# Schematic.net
KiCad netlist of a schematic drawn in EasyEDA
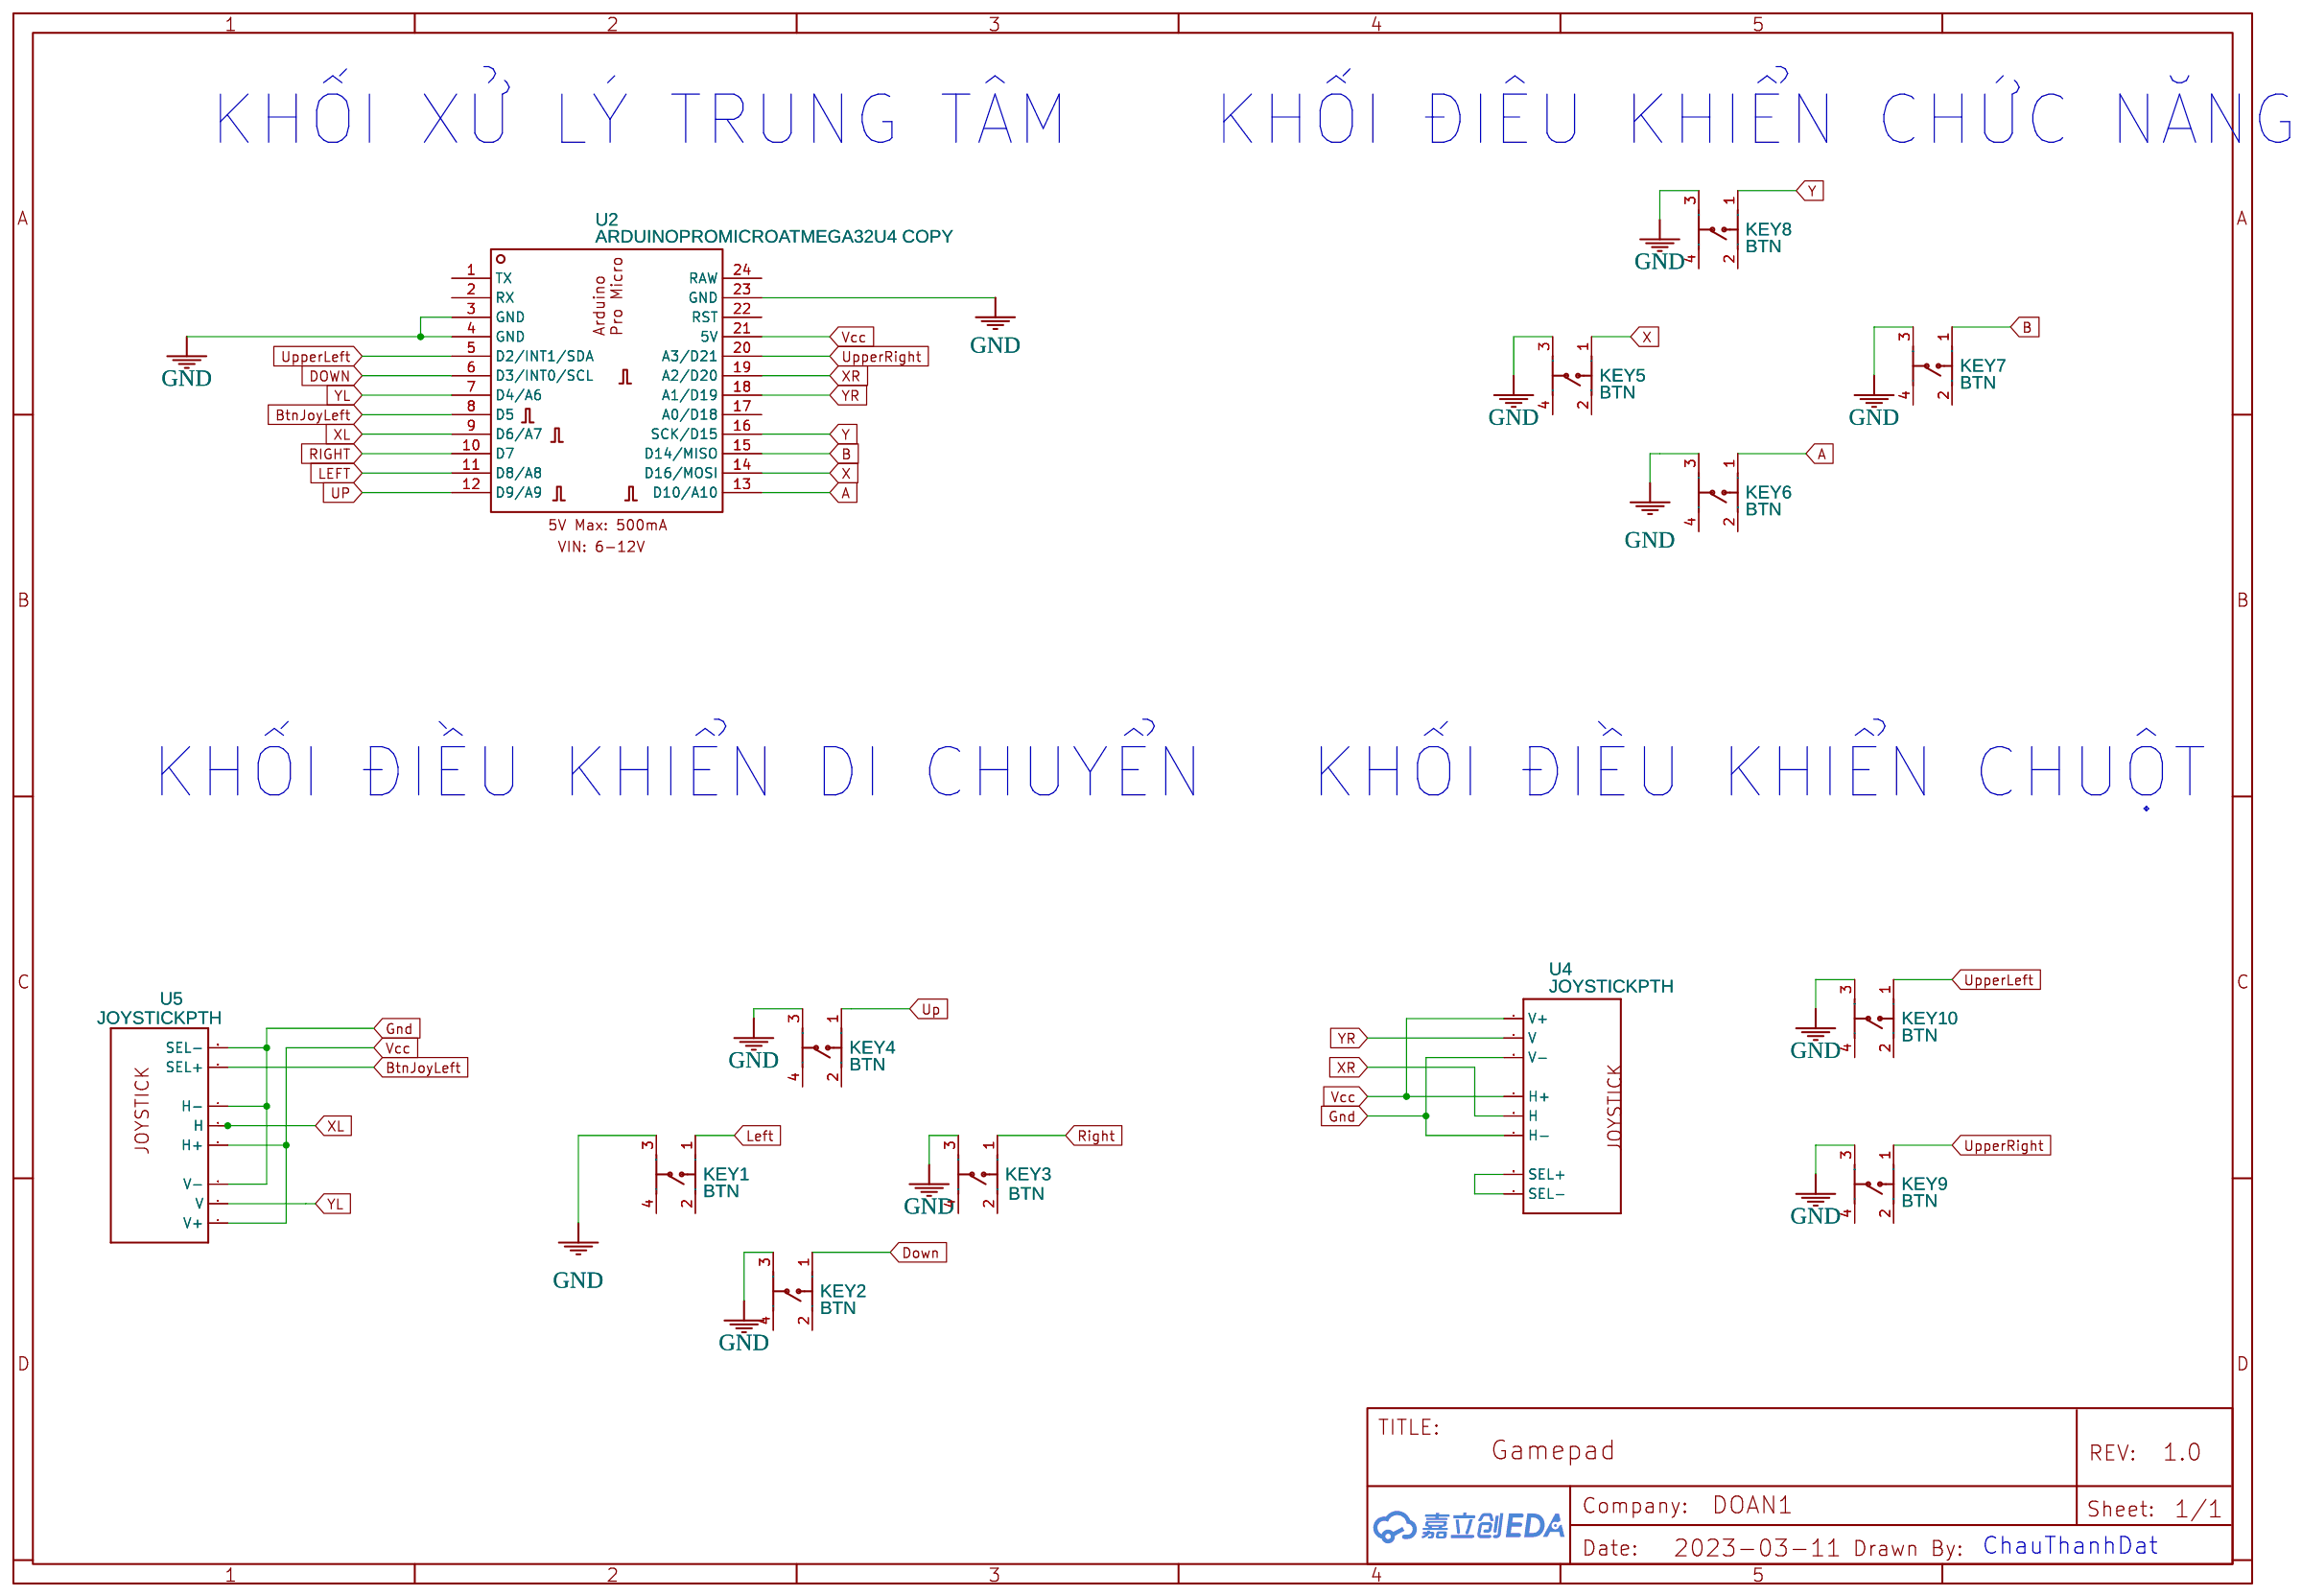
[diagram p0: schematic sheet]

(export (version "E")
  (design (tool "Eeschema 10.0.6"))
  (components
    (comp (ref "KEY1")
      (value "BTN")
      (fields
        (field (name "BOM_Manufacturer Part") "4pinTACTPCBTHTPushButton")
        (field (name "BOM_Supplier Part") "C9900003768")
      )
      (libsource (lib "") (part "4PINTACTPCBTHTPUSHBUTTON"))
    )
    (comp (ref "KEY2")
      (value "BTN")
      (fields
        (field (name "BOM_Manufacturer Part") "4pinTACTPCBTHTPushButton")
        (field (name "BOM_Supplier Part") "C9900003768")
      )
      (libsource (lib "") (part "4PINTACTPCBTHTPUSHBUTTON"))
    )
    (comp (ref "KEY3")
      (value "BTN")
      (fields
        (field (name "BOM_Manufacturer Part") "4pinTACTPCBTHTPushButton")
        (field (name "BOM_Supplier Part") "C9900003768")
      )
      (libsource (lib "") (part "4PINTACTPCBTHTPUSHBUTTON"))
    )
    (comp (ref "KEY4")
      (value "BTN")
      (fields
        (field (name "BOM_Manufacturer Part") "4pinTACTPCBTHTPushButton")
        (field (name "BOM_Supplier Part") "C9900003768")
      )
      (libsource (lib "") (part "4PINTACTPCBTHTPUSHBUTTON"))
    )
    (comp (ref "KEY5")
      (value "BTN")
      (fields
        (field (name "BOM_Manufacturer Part") "4pinTACTPCBTHTPushButton")
        (field (name "BOM_Supplier Part") "C9900003768")
      )
      (libsource (lib "") (part "4PINTACTPCBTHTPUSHBUTTON"))
    )
    (comp (ref "KEY6")
      (value "BTN")
      (fields
        (field (name "BOM_Manufacturer Part") "4pinTACTPCBTHTPushButton")
        (field (name "BOM_Supplier Part") "C9900003768")
      )
      (libsource (lib "") (part "4PINTACTPCBTHTPUSHBUTTON"))
    )
    (comp (ref "KEY7")
      (value "BTN")
      (fields
        (field (name "BOM_Manufacturer Part") "4pinTACTPCBTHTPushButton")
        (field (name "BOM_Supplier Part") "C9900003768")
      )
      (libsource (lib "") (part "4PINTACTPCBTHTPUSHBUTTON"))
    )
    (comp (ref "KEY8")
      (value "BTN")
      (fields
        (field (name "BOM_Manufacturer Part") "4pinTACTPCBTHTPushButton")
        (field (name "BOM_Supplier Part") "C9900003768")
      )
      (libsource (lib "") (part "4PINTACTPCBTHTPUSHBUTTON"))
    )
    (comp (ref "KEY9")
      (value "BTN")
      (fields
        (field (name "BOM_Manufacturer Part") "4pinTACTPCBTHTPushButton")
        (field (name "BOM_Supplier Part") "C9900003768")
      )
      (libsource (lib "") (part "4PINTACTPCBTHTPUSHBUTTON"))
    )
    (comp (ref "KEY10")
      (value "BTN")
      (fields
        (field (name "BOM_Manufacturer Part") "4pinTACTPCBTHTPushButton")
        (field (name "BOM_Supplier Part") "C9900003768")
      )
      (libsource (lib "") (part "4PINTACTPCBTHTPUSHBUTTON"))
    )
    (comp (ref "U2")
      (value "ARDUINOPROMICROATMEGA32U4 COPY")
      (libsource (lib "") (part "ARDUINOPROMICROATMEGA32U4 COPY"))
    )
    (comp (ref "U4") (value "JOYSTICKPTH") (libsource (lib "") (part "JOYSTICKPTH")))
    (comp (ref "U5") (value "JOYSTICKPTH") (libsource (lib "") (part "JOYSTICKPTH_1")))
  )
  (nets
    (net (code "1") (name "A") (class "Default")
      (node (ref "KEY6") (pin "1") (pinfunction "1_1") (pintype "unspecified"))
      (node (ref "U2") (pin "13") (pinfunction "D10/A10_13") (pintype "unspecified"))
    )
    (net (code "2") (name "B") (class "Default")
      (node (ref "KEY7") (pin "1") (pinfunction "1_1") (pintype "unspecified"))
      (node (ref "U2") (pin "15") (pinfunction "D14/MISO_15") (pintype "unspecified"))
    )
    (net (code "3") (name "BtnJoyLeft") (class "Default")
      (node (ref "U2") (pin "8") (pinfunction "D5_8") (pintype "unspecified"))
      (node (ref "U5") (pin "B1A") (pinfunction "SEL+_B1A") (pintype "unspecified"))
    )
    (net (code "4") (name "DOWN") (class "Default")
      (node (ref "U2") (pin "6") (pinfunction "D3/INT0/SCL_6") (pintype "unspecified"))
    )
    (net (code "5") (name "Down") (class "Default")
      (node (ref "KEY2") (pin "1") (pinfunction "1_1") (pintype "unspecified"))
    )
    (net (code "6") (name "GND") (class "Default")
      (node (ref "KEY1") (pin "3") (pinfunction "3_3") (pintype "unspecified"))
      (node (ref "KEY10") (pin "3") (pinfunction "3_3") (pintype "unspecified"))
      (node (ref "KEY2") (pin "3") (pinfunction "3_3") (pintype "unspecified"))
      (node (ref "KEY3") (pin "3") (pinfunction "3_3") (pintype "unspecified"))
      (node (ref "KEY4") (pin "3") (pinfunction "3_3") (pintype "unspecified"))
      (node (ref "KEY5") (pin "3") (pinfunction "3_3") (pintype "unspecified"))
      (node (ref "KEY6") (pin "3") (pinfunction "3_3") (pintype "unspecified"))
      (node (ref "KEY7") (pin "3") (pinfunction "3_3") (pintype "unspecified"))
      (node (ref "KEY8") (pin "3") (pinfunction "3_3") (pintype "unspecified"))
      (node (ref "KEY9") (pin "3") (pinfunction "3_3") (pintype "unspecified"))
      (node (ref "U2") (pin "23") (pinfunction "GND_23") (pintype "unspecified"))
      (node (ref "U2") (pin "3") (pinfunction "GND_3") (pintype "unspecified"))
      (node (ref "U2") (pin "4") (pinfunction "GND_4") (pintype "unspecified"))
    )
    (net (code "7") (name "Gnd") (class "Default")
      (node (ref "U4") (pin "H3") (pinfunction "H-_H3") (pintype "unspecified"))
      (node (ref "U4") (pin "V3") (pinfunction "V-_V3") (pintype "unspecified"))
      (node (ref "U5") (pin "B2A") (pinfunction "SEL-_B2A") (pintype "unspecified"))
      (node (ref "U5") (pin "H3") (pinfunction "H-_H3") (pintype "unspecified"))
      (node (ref "U5") (pin "V3") (pinfunction "V-_V3") (pintype "unspecified"))
    )
    (net (code "8") (name "LEFT") (class "Default")
      (node (ref "U2") (pin "11") (pinfunction "D8/A8_11") (pintype "unspecified"))
    )
    (net (code "9") (name "Left") (class "Default")
      (node (ref "KEY1") (pin "1") (pinfunction "1_1") (pintype "unspecified"))
    )
    (net (code "10") (name "Net-(U4-SEL+)") (class "Default")
      (node (ref "U4") (pin "B1A") (pinfunction "SEL+_B1A") (pintype "unspecified"))
      (node (ref "U4") (pin "B2A") (pinfunction "SEL-_B2A") (pintype "unspecified"))
    )
    (net (code "11") (name "RIGHT") (class "Default")
      (node (ref "U2") (pin "10") (pinfunction "D7_10") (pintype "unspecified"))
    )
    (net (code "12") (name "Right") (class "Default")
      (node (ref "KEY3") (pin "1") (pinfunction "1_1") (pintype "unspecified"))
    )
    (net (code "13") (name "UP") (class "Default")
      (node (ref "U2") (pin "12") (pinfunction "D9/A9_12") (pintype "unspecified"))
    )
    (net (code "14") (name "Up") (class "Default")
      (node (ref "KEY4") (pin "1") (pinfunction "1_1") (pintype "unspecified"))
    )
    (net (code "15") (name "UpperLeft") (class "Default")
      (node (ref "KEY10") (pin "1") (pinfunction "1_1") (pintype "unspecified"))
      (node (ref "U2") (pin "5") (pinfunction "D2/INT1/SDA_5") (pintype "unspecified"))
    )
    (net (code "16") (name "UpperRight") (class "Default")
      (node (ref "KEY9") (pin "1") (pinfunction "1_1") (pintype "unspecified"))
      (node (ref "U2") (pin "20") (pinfunction "A3/D21_20") (pintype "unspecified"))
    )
    (net (code "17") (name "Vcc") (class "Default")
      (node (ref "U2") (pin "21") (pinfunction "5V_21") (pintype "unspecified"))
      (node (ref "U4") (pin "H1") (pinfunction "H+_H1") (pintype "unspecified"))
      (node (ref "U4") (pin "V1") (pinfunction "V+_V1") (pintype "unspecified"))
      (node (ref "U5") (pin "H1") (pinfunction "H+_H1") (pintype "unspecified"))
      (node (ref "U5") (pin "V1") (pinfunction "V+_V1") (pintype "unspecified"))
    )
    (net (code "18") (name "X") (class "Default")
      (node (ref "KEY5") (pin "1") (pinfunction "1_1") (pintype "unspecified"))
      (node (ref "U2") (pin "14") (pinfunction "D16/MOSI_14") (pintype "unspecified"))
    )
    (net (code "19") (name "XL") (class "Default")
      (node (ref "U2") (pin "9") (pinfunction "D6/A7_9") (pintype "unspecified"))
      (node (ref "U5") (pin "H2") (pinfunction "H_H2") (pintype "unspecified"))
    )
    (net (code "20") (name "XR") (class "Default")
      (node (ref "U2") (pin "19") (pinfunction "A2/D20_19") (pintype "unspecified"))
      (node (ref "U4") (pin "H2") (pinfunction "H_H2") (pintype "unspecified"))
    )
    (net (code "21") (name "Y") (class "Default")
      (node (ref "KEY8") (pin "1") (pinfunction "1_1") (pintype "unspecified"))
      (node (ref "U2") (pin "16") (pinfunction "SCK/D15_16") (pintype "unspecified"))
    )
    (net (code "22") (name "YL") (class "Default")
      (node (ref "U2") (pin "7") (pinfunction "D4/A6_7") (pintype "unspecified"))
      (node (ref "U5") (pin "V2") (pinfunction "V_V2") (pintype "unspecified"))
    )
    (net (code "23") (name "YR") (class "Default")
      (node (ref "U2") (pin "18") (pinfunction "A1/D19_18") (pintype "unspecified"))
      (node (ref "U4") (pin "V2") (pinfunction "V_V2") (pintype "unspecified"))
    )
    (net (code "24") (name "unconnected-(KEY1-Pad2)") (class "Default")
      (node (ref "KEY1") (pin "2") (pinfunction "2_2") (pintype "unspecified"))
    )
    (net (code "25") (name "unconnected-(KEY1-Pad4)") (class "Default")
      (node (ref "KEY1") (pin "4") (pinfunction "4_4") (pintype "unspecified"))
    )
    (net (code "26") (name "unconnected-(KEY2-Pad2)") (class "Default")
      (node (ref "KEY2") (pin "2") (pinfunction "2_2") (pintype "unspecified"))
    )
    (net (code "27") (name "unconnected-(KEY2-Pad4)") (class "Default")
      (node (ref "KEY2") (pin "4") (pinfunction "4_4") (pintype "unspecified"))
    )
    (net (code "28") (name "unconnected-(KEY3-Pad2)") (class "Default")
      (node (ref "KEY3") (pin "2") (pinfunction "2_2") (pintype "unspecified"))
    )
    (net (code "29") (name "unconnected-(KEY3-Pad4)") (class "Default")
      (node (ref "KEY3") (pin "4") (pinfunction "4_4") (pintype "unspecified"))
    )
    (net (code "30") (name "unconnected-(KEY4-Pad2)") (class "Default")
      (node (ref "KEY4") (pin "2") (pinfunction "2_2") (pintype "unspecified"))
    )
    (net (code "31") (name "unconnected-(KEY4-Pad4)") (class "Default")
      (node (ref "KEY4") (pin "4") (pinfunction "4_4") (pintype "unspecified"))
    )
    (net (code "32") (name "unconnected-(KEY5-Pad2)") (class "Default")
      (node (ref "KEY5") (pin "2") (pinfunction "2_2") (pintype "unspecified"))
    )
    (net (code "33") (name "unconnected-(KEY5-Pad4)") (class "Default")
      (node (ref "KEY5") (pin "4") (pinfunction "4_4") (pintype "unspecified"))
    )
    (net (code "34") (name "unconnected-(KEY6-Pad2)") (class "Default")
      (node (ref "KEY6") (pin "2") (pinfunction "2_2") (pintype "unspecified"))
    )
    (net (code "35") (name "unconnected-(KEY6-Pad4)") (class "Default")
      (node (ref "KEY6") (pin "4") (pinfunction "4_4") (pintype "unspecified"))
    )
    (net (code "36") (name "unconnected-(KEY7-Pad2)") (class "Default")
      (node (ref "KEY7") (pin "2") (pinfunction "2_2") (pintype "unspecified"))
    )
    (net (code "37") (name "unconnected-(KEY7-Pad4)") (class "Default")
      (node (ref "KEY7") (pin "4") (pinfunction "4_4") (pintype "unspecified"))
    )
    (net (code "38") (name "unconnected-(KEY8-Pad2)") (class "Default")
      (node (ref "KEY8") (pin "2") (pinfunction "2_2") (pintype "unspecified"))
    )
    (net (code "39") (name "unconnected-(KEY8-Pad4)") (class "Default")
      (node (ref "KEY8") (pin "4") (pinfunction "4_4") (pintype "unspecified"))
    )
    (net (code "40") (name "unconnected-(KEY9-Pad2)") (class "Default")
      (node (ref "KEY9") (pin "2") (pinfunction "2_2") (pintype "unspecified"))
    )
    (net (code "41") (name "unconnected-(KEY9-Pad4)") (class "Default")
      (node (ref "KEY9") (pin "4") (pinfunction "4_4") (pintype "unspecified"))
    )
    (net (code "42") (name "unconnected-(KEY10-Pad2)") (class "Default")
      (node (ref "KEY10") (pin "2") (pinfunction "2_2") (pintype "unspecified"))
    )
    (net (code "43") (name "unconnected-(KEY10-Pad4)") (class "Default")
      (node (ref "KEY10") (pin "4") (pinfunction "4_4") (pintype "unspecified"))
    )
    (net (code "44") (name "unconnected-(U2-A0{slash}D18-Pad17)") (class "Default")
      (node (ref "U2") (pin "17") (pinfunction "A0/D18_17") (pintype "unspecified"))
    )
    (net (code "45") (name "unconnected-(U2-RAW-Pad24)") (class "Default")
      (node (ref "U2") (pin "24") (pinfunction "RAW_24") (pintype "unspecified"))
    )
    (net (code "46") (name "unconnected-(U2-RST-Pad22)") (class "Default")
      (node (ref "U2") (pin "22") (pinfunction "RST_22") (pintype "unspecified"))
    )
    (net (code "47") (name "unconnected-(U2-RX-Pad2)") (class "Default")
      (node (ref "U2") (pin "2") (pinfunction "RX_2") (pintype "unspecified"))
    )
    (net (code "48") (name "unconnected-(U2-TX-Pad1)") (class "Default")
      (node (ref "U2") (pin "1") (pinfunction "TX_1") (pintype "unspecified"))
    )
  )
)
